# Schematic.net
KiCad netlist of a schematic drawn in Altium Designer
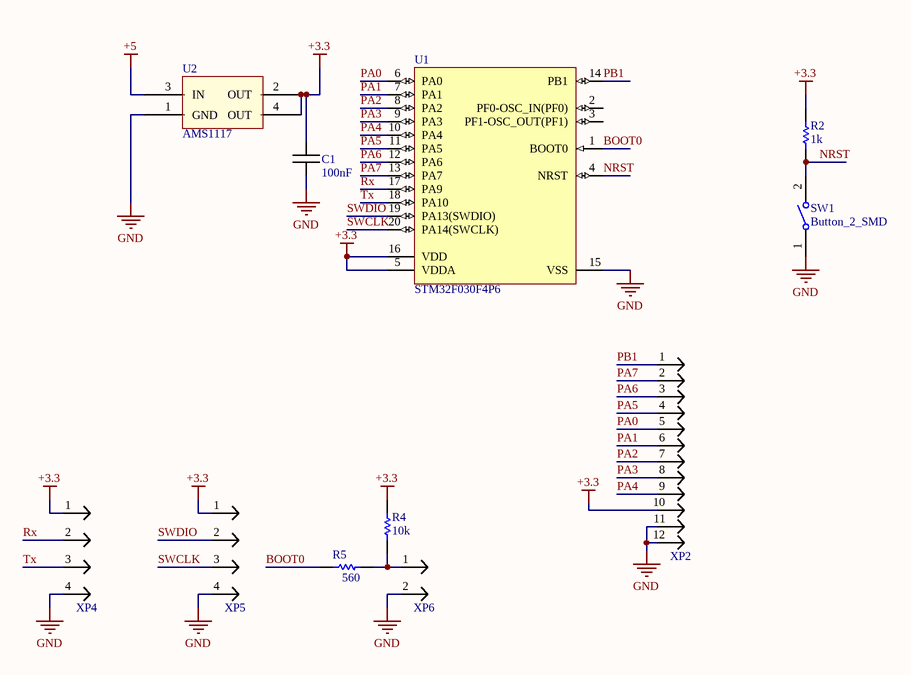
[diagram p0: Schematic.SchDoc]

(export (version "E")
  (design (tool "Eeschema 10.0.6"))
  (components
    (comp (ref "C1")
      (value "CAP_SMD")
      (footprint "CAP0805")
      (description "Ceramic capacitor, 0805")
      (fields (field (name "VAL") "100nF"))
      (libsource (lib "altium-import") (part "root_1_CAP_SMD_"))
    )
    (comp (ref "R2")
      (value "RES_SMD")
      (footprint "RES0805")
      (fields (field (name "VAL") "1k"))
      (libsource (lib "altium-import") (part "root_1_RES_SMD_"))
    )
    (comp (ref "R4")
      (value "RES_SMD")
      (footprint "RES0805")
      (fields (field (name "VAL") "10k"))
      (libsource (lib "altium-import") (part "root_1_RES_SMD_"))
    )
    (comp (ref "R5")
      (value "RES_SMD")
      (footprint "RES0805")
      (fields (field (name "VAL") "560"))
      (libsource (lib "altium-import") (part "root_0_RES_SMD_"))
    )
    (comp (ref "SW1")
      (value "Button_2_SMD")
      (footprint "SMD_BUT_6.3mm")
      (fields (field (name "MANUFACTURER") "TE Connectivity"))
      (libsource (lib "altium-import") (part "root_1_Button_2_SMD_"))
    )
    (comp (ref "U1")
      (value "STM32F030F4P6")
      (footprint "STM-TSSOP20_N")
      (libsource (lib "altium-import") (part "root_0_STM32F030F4P6_"))
    )
    (comp (ref "U2")
      (value "AMS1117")
      (footprint "SOT223-4")
      (description "Voltage regulator")
      (libsource (lib "altium-import") (part "root_0_AMS1117_"))
    )
    (comp (ref "XP2")
      (value "PLS-12")
      (footprint "PLS-12")
      (libsource (lib "altium-import") (part "root_0_PLS-12_"))
    )
    (comp (ref "XP4")
      (value "PLS-04")
      (footprint "PLS-04")
      (libsource (lib "altium-import") (part "root_0_PLS-04_"))
    )
    (comp (ref "XP5")
      (value "PLS-04")
      (footprint "PLS-04")
      (libsource (lib "altium-import") (part "root_0_PLS-04_"))
    )
    (comp (ref "XP6")
      (value "PLS-02")
      (footprint "PLS-02")
      (libsource (lib "altium-import") (part "root_0_PLS-02_"))
    )
  )
  (nets
    (net (code "1") (name "+3.3") (class "Default")
      (node (ref "C1") (pin "2") (pinfunction "2_2") (pintype "passive"))
      (node (ref "R2") (pin "2") (pinfunction "2_2") (pintype "passive"))
      (node (ref "R4") (pin "2") (pinfunction "2_2") (pintype "passive"))
      (node (ref "U1") (pin "16") (pinfunction "VDD_16") (pintype "power_in"))
      (node (ref "U1") (pin "5") (pinfunction "VDDA_5") (pintype "power_in"))
      (node (ref "U2") (pin "2") (pinfunction "OUT_2") (pintype "passive"))
      (node (ref "U2") (pin "4") (pinfunction "OUT_4") (pintype "passive"))
      (node (ref "XP2") (pin "10") (pinfunction "10_10") (pintype "passive"))
      (node (ref "XP4") (pin "1") (pinfunction "1_1") (pintype "passive"))
      (node (ref "XP5") (pin "1") (pinfunction "1_1") (pintype "passive"))
    )
    (net (code "2") (name "+5") (class "Default")
      (node (ref "U2") (pin "3") (pinfunction "IN_3") (pintype "passive"))
    )
    (net (code "3") (name "/BOOT0") (class "Default")
      (node (ref "R5") (pin "1") (pinfunction "1_1") (pintype "passive"))
      (node (ref "U1") (pin "1") (pinfunction "BOOT0_1") (pintype "input"))
    )
    (net (code "4") (name "/NRST") (class "Default")
      (node (ref "R2") (pin "1") (pinfunction "1_1") (pintype "passive"))
      (node (ref "SW1") (pin "2") (pinfunction "2_2") (pintype "passive"))
      (node (ref "U1") (pin "4") (pinfunction "NRST_4") (pintype "bidirectional"))
    )
    (net (code "5") (name "/PA0") (class "Default")
      (node (ref "U1") (pin "6") (pinfunction "PA0_6") (pintype "bidirectional"))
      (node (ref "XP2") (pin "5") (pinfunction "5_5") (pintype "passive"))
    )
    (net (code "6") (name "/PA1") (class "Default")
      (node (ref "U1") (pin "7") (pinfunction "PA1_7") (pintype "bidirectional"))
      (node (ref "XP2") (pin "6") (pinfunction "6_6") (pintype "passive"))
    )
    (net (code "7") (name "/PA2") (class "Default")
      (node (ref "U1") (pin "8") (pinfunction "PA2_8") (pintype "bidirectional"))
      (node (ref "XP2") (pin "7") (pinfunction "7_7") (pintype "passive"))
    )
    (net (code "8") (name "/PA3") (class "Default")
      (node (ref "U1") (pin "9") (pinfunction "PA3_9") (pintype "bidirectional"))
      (node (ref "XP2") (pin "8") (pinfunction "8_8") (pintype "passive"))
    )
    (net (code "9") (name "/PA4") (class "Default")
      (node (ref "U1") (pin "10") (pinfunction "PA4_10") (pintype "bidirectional"))
      (node (ref "XP2") (pin "9") (pinfunction "9_9") (pintype "passive"))
    )
    (net (code "10") (name "/PA5") (class "Default")
      (node (ref "U1") (pin "11") (pinfunction "PA5_11") (pintype "bidirectional"))
      (node (ref "XP2") (pin "4") (pinfunction "4_4") (pintype "passive"))
    )
    (net (code "11") (name "/PA6") (class "Default")
      (node (ref "U1") (pin "12") (pinfunction "PA6_12") (pintype "bidirectional"))
      (node (ref "XP2") (pin "3") (pinfunction "3_3") (pintype "passive"))
    )
    (net (code "12") (name "/PA7") (class "Default")
      (node (ref "U1") (pin "13") (pinfunction "PA7_13") (pintype "bidirectional"))
      (node (ref "XP2") (pin "2") (pinfunction "2_2") (pintype "passive"))
    )
    (net (code "13") (name "/PB1") (class "Default")
      (node (ref "U1") (pin "14") (pinfunction "PB1_14") (pintype "bidirectional"))
      (node (ref "XP2") (pin "1") (pinfunction "1_1") (pintype "passive"))
    )
    (net (code "14") (name "/Rx") (class "Default")
      (node (ref "U1") (pin "17") (pinfunction "PA9_17") (pintype "bidirectional"))
      (node (ref "XP4") (pin "2") (pinfunction "2_2") (pintype "passive"))
    )
    (net (code "15") (name "/SWCLK") (class "Default")
      (node (ref "U1") (pin "20") (pinfunction "PA14(SWCLK)_20") (pintype "bidirectional"))
      (node (ref "XP5") (pin "3") (pinfunction "3_3") (pintype "passive"))
    )
    (net (code "16") (name "/SWDIO") (class "Default")
      (node (ref "U1") (pin "19") (pinfunction "PA13(SWDIO)_19") (pintype "bidirectional"))
      (node (ref "XP5") (pin "2") (pinfunction "2_2") (pintype "passive"))
    )
    (net (code "17") (name "/Tx") (class "Default")
      (node (ref "U1") (pin "18") (pinfunction "PA10_18") (pintype "bidirectional"))
      (node (ref "XP4") (pin "3") (pinfunction "3_3") (pintype "passive"))
    )
    (net (code "18") (name "GND") (class "Default")
      (node (ref "C1") (pin "1") (pinfunction "1_1") (pintype "passive"))
      (node (ref "SW1") (pin "1") (pinfunction "1_1") (pintype "passive"))
      (node (ref "U1") (pin "15") (pinfunction "VSS_15") (pintype "power_in"))
      (node (ref "U2") (pin "1") (pinfunction "GND_1") (pintype "passive"))
      (node (ref "XP2") (pin "11") (pinfunction "11_11") (pintype "passive"))
      (node (ref "XP2") (pin "12") (pinfunction "12_12") (pintype "passive"))
      (node (ref "XP4") (pin "4") (pinfunction "4_4") (pintype "passive"))
      (node (ref "XP5") (pin "4") (pinfunction "4_4") (pintype "passive"))
      (node (ref "XP6") (pin "2") (pinfunction "2_2") (pintype "passive"))
    )
    (net (code "19") (name "Net-(R4-Pad1)") (class "Default")
      (node (ref "R4") (pin "1") (pinfunction "1_1") (pintype "passive"))
      (node (ref "R5") (pin "2") (pinfunction "2_2") (pintype "passive"))
      (node (ref "XP6") (pin "1") (pinfunction "1_1") (pintype "passive"))
    )
    (net (code "20") (name "unconnected-(U1-PF0-OSC_IN(PF0)-Pad2)") (class "Default")
      (node (ref "U1") (pin "2") (pinfunction "PF0-OSC_IN(PF0)_2") (pintype "bidirectional"))
    )
    (net (code "21") (name "unconnected-(U1-PF1-OSC_OUT(PF1)-Pad3)") (class "Default")
      (node (ref "U1") (pin "3") (pinfunction "PF1-OSC_OUT(PF1)_3") (pintype "bidirectional"))
    )
  )
)
